# LEDs.net
KiCad netlist of a schematic drawn in EAGLE
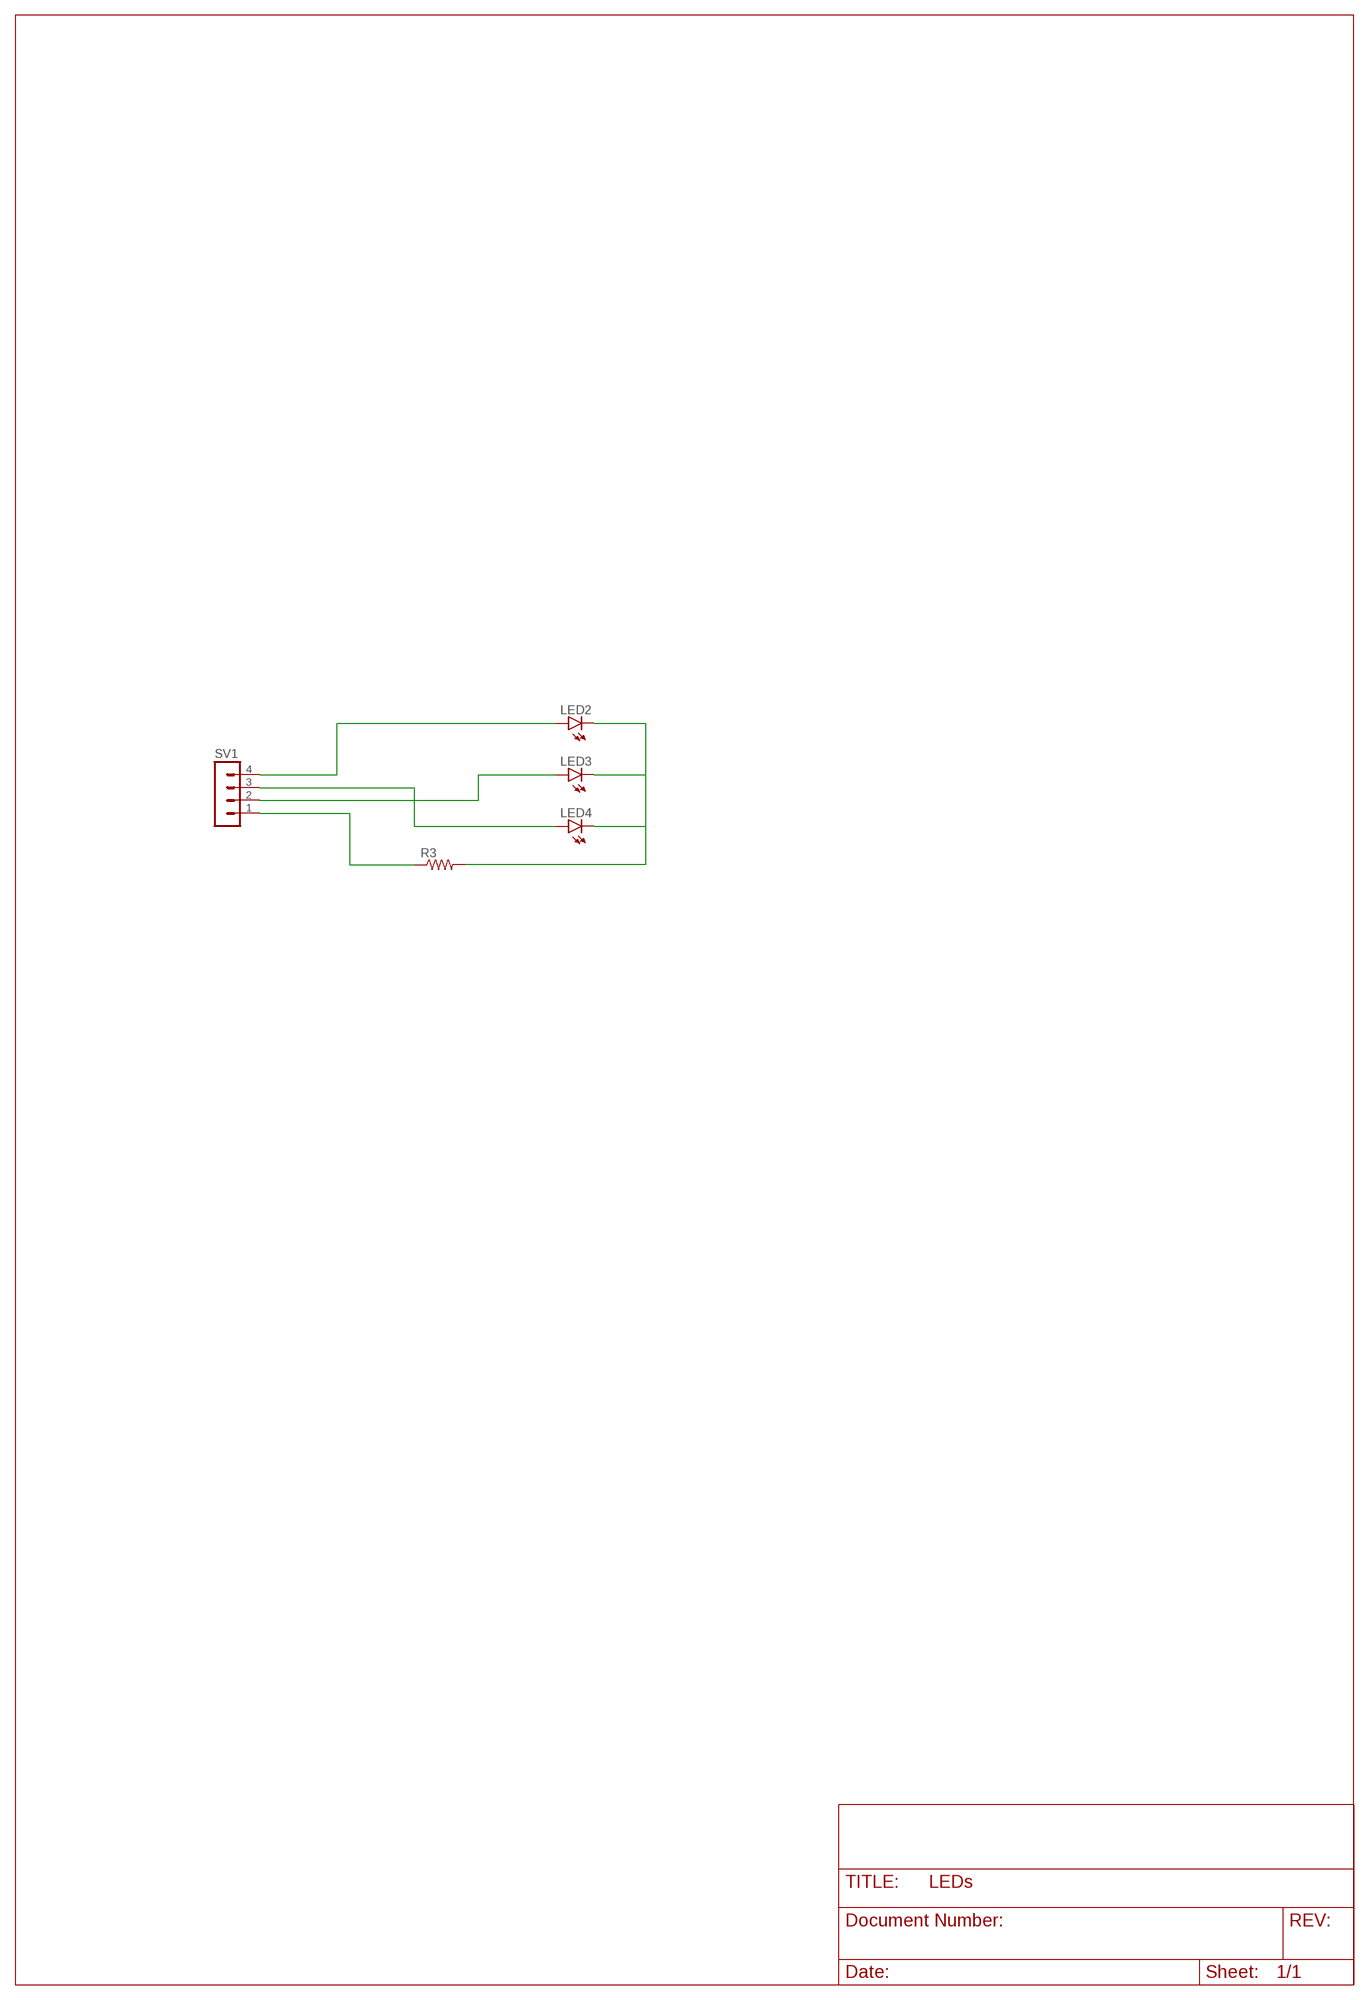
[diagram p0: schematic, sheet 1]

(export (version "E")
  (design (tool "Eeschema 10.0.6"))
  (components
    (comp (ref "LED2")
      (value "LED5MM")
      (footprint "eagle-import:LED5MM")
      (libsource (lib "eagle-import") (part "LED5MM"))
    )
    (comp (ref "LED3")
      (value "LED5MM")
      (footprint "eagle-import:LED5MM")
      (libsource (lib "eagle-import") (part "LED5MM"))
    )
    (comp (ref "LED4")
      (value "LED5MM")
      (footprint "eagle-import:LED5MM")
      (libsource (lib "eagle-import") (part "LED5MM"))
    )
    (comp (ref "R3")
      (value "R-US_0204/7")
      (footprint "eagle-import:0204_7")
      (libsource (lib "eagle-import") (part "R-US_0204/7"))
    )
    (comp (ref "SV1")
      (value "MA04-1")
      (footprint "eagle-import:MA04-1")
      (libsource (lib "eagle-import") (part "MA04-1"))
    )
  )
  (nets
    (net (code "1") (name "Net-(LED2-C)") (class "Default")
      (node (ref "LED2") (pin "K") (pinfunction "C_K") (pintype "passive"))
      (node (ref "LED3") (pin "K") (pinfunction "C_K") (pintype "passive"))
      (node (ref "LED4") (pin "K") (pinfunction "C_K") (pintype "passive"))
      (node (ref "R3") (pin "2") (pinfunction "2_2") (pintype "passive"))
    )
    (net (code "2") (name "Net-(LED2-PadA)") (class "Default")
      (node (ref "LED2") (pin "A") (pinfunction "A_A") (pintype "passive"))
      (node (ref "SV1") (pin "4") (pinfunction "4_4") (pintype "passive"))
    )
    (net (code "3") (name "Net-(LED3-PadA)") (class "Default")
      (node (ref "LED3") (pin "A") (pinfunction "A_A") (pintype "passive"))
      (node (ref "SV1") (pin "2") (pinfunction "2_2") (pintype "passive"))
    )
    (net (code "4") (name "Net-(LED4-PadA)") (class "Default")
      (node (ref "LED4") (pin "A") (pinfunction "A_A") (pintype "passive"))
      (node (ref "SV1") (pin "3") (pinfunction "3_3") (pintype "passive"))
    )
    (net (code "5") (name "Net-(R3-Pad1)") (class "Default")
      (node (ref "R3") (pin "1") (pinfunction "1_1") (pintype "passive"))
      (node (ref "SV1") (pin "1") (pinfunction "1_1") (pintype "passive"))
    )
  )
)
